# BT_Lamp_Controller.net
KiCad netlist of a schematic drawn in Altium Designer
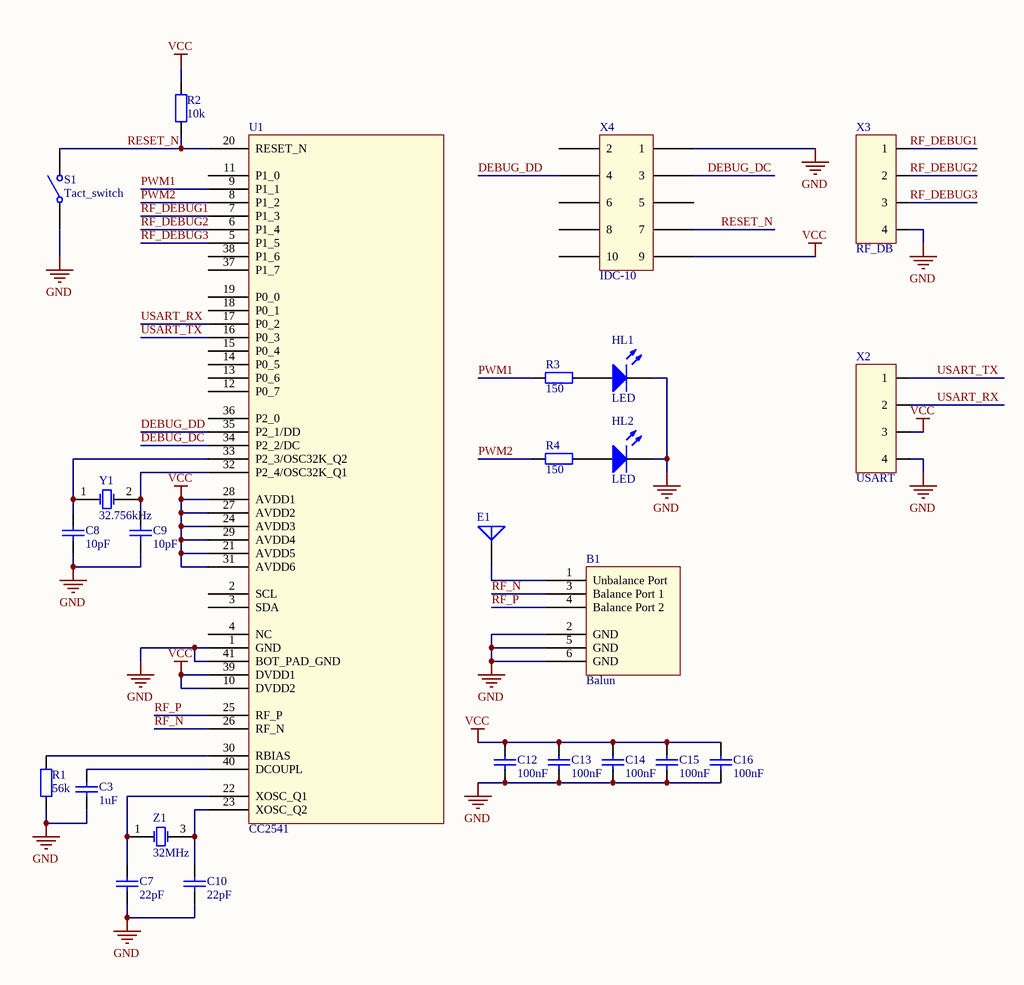
[diagram p0: BT_Lamp_Controller.SchDoc]

(export (version "E")
  (design (tool "Eeschema 10.0.6"))
  (components
    (comp (ref "B1")
      (value "Balun")
      (footprint "A_H_pcb_lib:2.4 Balun 50Ohm LFB182G45BG2D280")
      (libsource (lib "A_H_sch_lib") (part "2.4 Balun 50Ohm LFB182G45BG2D280"))
    )
    (comp (ref "C3")
      (value "1uF")
      (footprint "A_H_pcb_lib:C0603")
      (libsource (lib "A_H_sch_lib") (part "Condensator"))
    )
    (comp (ref "C7")
      (value "22pF")
      (footprint "A_H_pcb_lib:C0603")
      (libsource (lib "A_H_sch_lib") (part "Condensator"))
    )
    (comp (ref "C8")
      (value "10pF")
      (footprint "A_H_pcb_lib:C0603")
      (libsource (lib "A_H_sch_lib") (part "Condensator"))
    )
    (comp (ref "C9")
      (value "10pF")
      (footprint "A_H_pcb_lib:C0603")
      (libsource (lib "A_H_sch_lib") (part "Condensator"))
    )
    (comp (ref "C10")
      (value "22pF")
      (footprint "A_H_pcb_lib:C0603")
      (libsource (lib "A_H_sch_lib") (part "Condensator"))
    )
    (comp (ref "C12")
      (value "100nF")
      (footprint "A_H_pcb_lib:C0603")
      (libsource (lib "A_H_sch_lib") (part "Condensator"))
    )
    (comp (ref "C13")
      (value "100nF")
      (footprint "A_H_pcb_lib:C0603")
      (libsource (lib "A_H_sch_lib") (part "Condensator"))
    )
    (comp (ref "C14")
      (value "100nF")
      (footprint "A_H_pcb_lib:C0603")
      (libsource (lib "A_H_sch_lib") (part "Condensator"))
    )
    (comp (ref "C15")
      (value "100nF")
      (footprint "A_H_pcb_lib:C0603")
      (libsource (lib "A_H_sch_lib") (part "Condensator"))
    )
    (comp (ref "C16")
      (value "100nF")
      (footprint "A_H_pcb_lib:C0603")
      (libsource (lib "A_H_sch_lib") (part "Condensator"))
    )
    (comp (ref "E1")
      (value "Antenna")
      (footprint "A_H_pcb_lib:2.4 INF Antenna")
      (libsource (lib "A_H_sch_lib") (part "Antenna"))
    )
    (comp (ref "HL1")
      (value "LED")
      (footprint "A_H_pcb_lib:LED_0805")
      (libsource (lib "A_H_sch_lib") (part "LED"))
    )
    (comp (ref "HL2")
      (value "LED")
      (footprint "A_H_pcb_lib:LED_0805")
      (libsource (lib "A_H_sch_lib") (part "LED"))
    )
    (comp (ref "R1") (value "56k") (footprint "A_H_pcb_lib:R0603") (libsource (lib "") (part "Resistor_1")))
    (comp (ref "R2") (value "10k") (footprint "A_H_pcb_lib:R0603") (libsource (lib "") (part "Resistor_1")))
    (comp (ref "R3")
      (value "150")
      (footprint "A_H_pcb_lib:R0603")
      (libsource (lib "A_H_sch_lib") (part "Resistor"))
    )
    (comp (ref "R4")
      (value "150")
      (footprint "A_H_pcb_lib:R0603")
      (libsource (lib "A_H_sch_lib") (part "Resistor"))
    )
    (comp (ref "S1")
      (value "Tact_switch")
      (footprint "Tact_switch_smd")
      (libsource (lib "A_H_sch_lib") (part "Tact_switch"))
    )
    (comp (ref "U1")
      (value "CC2541")
      (footprint "A_H_pcb_lib:QFN40 6x6 0.5pitch")
      (libsource (lib "A_H_sch_lib") (part "CC2541"))
    )
    (comp (ref "X2")
      (value "USART")
      (footprint "Pins 4x2.54")
      (libsource (lib "A_H_sch_lib") (part "Pins 4x2.54"))
    )
    (comp (ref "X3")
      (value "RF_DB")
      (footprint "Pins 4x2.54")
      (libsource (lib "A_H_sch_lib") (part "Pins 4x2.54"))
    )
    (comp (ref "X4")
      (value "IDC-10")
      (footprint "A_H_pcb_lib:IDC-10")
      (libsource (lib "A_H_sch_lib") (part "IDC-10"))
    )
    (comp (ref "Y1")
      (value "32.756kHz")
      (footprint "Geyer KX - 327S 32.768kHz")
      (libsource (lib "A_H_sch_lib") (part "Crystal Oscillator"))
    )
    (comp (ref "Z1")
      (value "32MHz")
      (footprint "kx 13 12MHz")
      (libsource (lib "A_H_sch_lib") (part "KX 13 Geyer"))
    )
  )
  (nets
    (net (code "1") (name "/DEBUG_DC") (class "Default")
      (node (ref "U1") (pin "34") (pinfunction "P2_2/DC_34") (pintype "passive"))
      (node (ref "X4") (pin "3") (pinfunction "3_3") (pintype "passive"))
    )
    (net (code "2") (name "/DEBUG_DD") (class "Default")
      (node (ref "U1") (pin "35") (pinfunction "P2_1/DD_35") (pintype "passive"))
      (node (ref "X4") (pin "4") (pinfunction "4_4") (pintype "passive"))
    )
    (net (code "3") (name "/PWM1") (class "Default")
      (node (ref "R3") (pin "2") (pinfunction "2_2") (pintype "passive"))
      (node (ref "U1") (pin "9") (pinfunction "P1_1_9") (pintype "passive"))
    )
    (net (code "4") (name "/PWM2") (class "Default")
      (node (ref "R4") (pin "2") (pinfunction "2_2") (pintype "passive"))
      (node (ref "U1") (pin "8") (pinfunction "P1_2_8") (pintype "passive"))
    )
    (net (code "5") (name "/RESET_N") (class "Default")
      (node (ref "R2") (pin "1") (pinfunction "1_1") (pintype "passive"))
      (node (ref "S1") (pin "2") (pinfunction "NO_2") (pintype "passive"))
      (node (ref "U1") (pin "20") (pinfunction "RESET_N_20") (pintype "passive"))
      (node (ref "X4") (pin "7") (pinfunction "7_7") (pintype "passive"))
    )
    (net (code "6") (name "/RF_DEBUG1") (class "Default")
      (node (ref "U1") (pin "7") (pinfunction "P1_3_7") (pintype "passive"))
      (node (ref "X3") (pin "1") (pinfunction "1_1") (pintype "passive"))
    )
    (net (code "7") (name "/RF_DEBUG2") (class "Default")
      (node (ref "U1") (pin "6") (pinfunction "P1_4_6") (pintype "passive"))
      (node (ref "X3") (pin "2") (pinfunction "2_2") (pintype "passive"))
    )
    (net (code "8") (name "/RF_DEBUG3") (class "Default")
      (node (ref "U1") (pin "5") (pinfunction "P1_5_5") (pintype "passive"))
      (node (ref "X3") (pin "3") (pinfunction "3_3") (pintype "passive"))
    )
    (net (code "9") (name "/RF_N") (class "Default")
      (node (ref "B1") (pin "3") (pinfunction "Balance_Port_1_3") (pintype "passive"))
      (node (ref "U1") (pin "26") (pinfunction "RF_N_26") (pintype "passive"))
    )
    (net (code "10") (name "/RF_P") (class "Default")
      (node (ref "B1") (pin "4") (pinfunction "Balance_Port_2_4") (pintype "passive"))
      (node (ref "U1") (pin "25") (pinfunction "RF_P_25") (pintype "passive"))
    )
    (net (code "11") (name "/USART_RX") (class "Default")
      (node (ref "U1") (pin "17") (pinfunction "P0_2_17") (pintype "passive"))
      (node (ref "X2") (pin "2") (pinfunction "2_2") (pintype "passive"))
    )
    (net (code "12") (name "/USART_TX") (class "Default")
      (node (ref "U1") (pin "16") (pinfunction "P0_3_16") (pintype "passive"))
      (node (ref "X2") (pin "1") (pinfunction "1_1") (pintype "passive"))
    )
    (net (code "13") (name "GND") (class "Default")
      (node (ref "B1") (pin "2") (pinfunction "GND_2") (pintype "passive"))
      (node (ref "B1") (pin "5") (pinfunction "GND_5") (pintype "passive"))
      (node (ref "B1") (pin "6") (pinfunction "GND_6") (pintype "passive"))
      (node (ref "C10") (pin "1") (pinfunction "1_1") (pintype "passive"))
      (node (ref "C12") (pin "2") (pinfunction "2_2") (pintype "passive"))
      (node (ref "C13") (pin "2") (pinfunction "2_2") (pintype "passive"))
      (node (ref "C14") (pin "2") (pinfunction "2_2") (pintype "passive"))
      (node (ref "C15") (pin "2") (pinfunction "2_2") (pintype "passive"))
      (node (ref "C16") (pin "2") (pinfunction "2_2") (pintype "passive"))
      (node (ref "C3") (pin "1") (pinfunction "1_1") (pintype "passive"))
      (node (ref "C7") (pin "1") (pinfunction "1_1") (pintype "passive"))
      (node (ref "C8") (pin "1") (pinfunction "1_1") (pintype "passive"))
      (node (ref "C9") (pin "1") (pinfunction "1_1") (pintype "passive"))
      (node (ref "HL1") (pin "2") (pinfunction "K_2") (pintype "passive"))
      (node (ref "HL2") (pin "2") (pinfunction "K_2") (pintype "passive"))
      (node (ref "R1") (pin "1") (pinfunction "1_1") (pintype "passive"))
      (node (ref "S1") (pin "1") (pinfunction "COMMON_1") (pintype "passive"))
      (node (ref "U1") (pin "1") (pinfunction "GND_1") (pintype "passive"))
      (node (ref "U1") (pin "41") (pinfunction "BOT_PAD_GND_41") (pintype "passive"))
      (node (ref "X2") (pin "4") (pinfunction "4_4") (pintype "passive"))
      (node (ref "X3") (pin "4") (pinfunction "4_4") (pintype "passive"))
      (node (ref "X4") (pin "1") (pinfunction "1_1") (pintype "passive"))
    )
    (net (code "14") (name "Net-(B1-Unbalance_Port)") (class "Default")
      (node (ref "B1") (pin "1") (pinfunction "Unbalance_Port_1") (pintype "passive"))
      (node (ref "E1") (pin "1") (pinfunction "A_1") (pintype "passive"))
    )
    (net (code "15") (name "Net-(HL1-A)") (class "Default")
      (node (ref "HL1") (pin "1") (pinfunction "A_1") (pintype "passive"))
      (node (ref "R3") (pin "1") (pinfunction "1_1") (pintype "passive"))
    )
    (net (code "16") (name "Net-(HL2-A)") (class "Default")
      (node (ref "HL2") (pin "1") (pinfunction "A_1") (pintype "passive"))
      (node (ref "R4") (pin "1") (pinfunction "1_1") (pintype "passive"))
    )
    (net (code "17") (name "Net-(U1-DCOUPL)") (class "Default")
      (node (ref "C3") (pin "2") (pinfunction "2_2") (pintype "passive"))
      (node (ref "U1") (pin "40") (pinfunction "DCOUPL_40") (pintype "passive"))
    )
    (net (code "18") (name "Net-(U1-P2_3{slash}OSC32K_Q2)") (class "Default")
      (node (ref "C8") (pin "2") (pinfunction "2_2") (pintype "passive"))
      (node (ref "U1") (pin "33") (pinfunction "P2_3/OSC32K_Q2_33") (pintype "passive"))
      (node (ref "Y1") (pin "1") (pinfunction "OSC1_1") (pintype "passive"))
    )
    (net (code "19") (name "Net-(U1-P2_4{slash}OSC32K_Q1)") (class "Default")
      (node (ref "C9") (pin "2") (pinfunction "2_2") (pintype "passive"))
      (node (ref "U1") (pin "32") (pinfunction "P2_4/OSC32K_Q1_32") (pintype "passive"))
      (node (ref "Y1") (pin "2") (pinfunction "OSC2_2") (pintype "passive"))
    )
    (net (code "20") (name "Net-(U1-RBIAS)") (class "Default")
      (node (ref "R1") (pin "2") (pinfunction "2_2") (pintype "passive"))
      (node (ref "U1") (pin "30") (pinfunction "RBIAS_30") (pintype "passive"))
    )
    (net (code "21") (name "Net-(U1-XOSC_Q1)") (class "Default")
      (node (ref "C7") (pin "2") (pinfunction "2_2") (pintype "passive"))
      (node (ref "U1") (pin "22") (pinfunction "XOSC_Q1_22") (pintype "passive"))
      (node (ref "Z1") (pin "1") (pinfunction "OSC1_1") (pintype "passive"))
    )
    (net (code "22") (name "Net-(U1-XOSC_Q2)") (class "Default")
      (node (ref "C10") (pin "2") (pinfunction "2_2") (pintype "passive"))
      (node (ref "U1") (pin "23") (pinfunction "XOSC_Q2_23") (pintype "passive"))
      (node (ref "Z1") (pin "3") (pinfunction "OSC2_3") (pintype "passive"))
    )
    (net (code "23") (name "VCC") (class "Default")
      (node (ref "C12") (pin "1") (pinfunction "1_1") (pintype "passive"))
      (node (ref "C13") (pin "1") (pinfunction "1_1") (pintype "passive"))
      (node (ref "C14") (pin "1") (pinfunction "1_1") (pintype "passive"))
      (node (ref "C15") (pin "1") (pinfunction "1_1") (pintype "passive"))
      (node (ref "C16") (pin "1") (pinfunction "1_1") (pintype "passive"))
      (node (ref "R2") (pin "2") (pinfunction "2_2") (pintype "passive"))
      (node (ref "U1") (pin "10") (pinfunction "DVDD2_10") (pintype "passive"))
      (node (ref "U1") (pin "21") (pinfunction "AVDD5_21") (pintype "passive"))
      (node (ref "U1") (pin "24") (pinfunction "AVDD3_24") (pintype "passive"))
      (node (ref "U1") (pin "27") (pinfunction "AVDD2_27") (pintype "passive"))
      (node (ref "U1") (pin "28") (pinfunction "AVDD1_28") (pintype "passive"))
      (node (ref "U1") (pin "29") (pinfunction "AVDD4_29") (pintype "passive"))
      (node (ref "U1") (pin "31") (pinfunction "AVDD6_31") (pintype "passive"))
      (node (ref "U1") (pin "39") (pinfunction "DVDD1_39") (pintype "passive"))
      (node (ref "X2") (pin "3") (pinfunction "3_3") (pintype "passive"))
      (node (ref "X4") (pin "9") (pinfunction "9_9") (pintype "passive"))
    )
    (net (code "24") (name "unconnected-(U1-NC-Pad4)") (class "Default")
      (node (ref "U1") (pin "4") (pinfunction "NC_4") (pintype "passive"))
    )
    (net (code "25") (name "unconnected-(U1-P0_0-Pad19)") (class "Default")
      (node (ref "U1") (pin "19") (pinfunction "P0_0_19") (pintype "passive"))
    )
    (net (code "26") (name "unconnected-(U1-P0_1-Pad18)") (class "Default")
      (node (ref "U1") (pin "18") (pinfunction "P0_1_18") (pintype "passive"))
    )
    (net (code "27") (name "unconnected-(U1-P0_4-Pad15)") (class "Default")
      (node (ref "U1") (pin "15") (pinfunction "P0_4_15") (pintype "passive"))
    )
    (net (code "28") (name "unconnected-(U1-P0_5-Pad14)") (class "Default")
      (node (ref "U1") (pin "14") (pinfunction "P0_5_14") (pintype "passive"))
    )
    (net (code "29") (name "unconnected-(U1-P0_6-Pad13)") (class "Default")
      (node (ref "U1") (pin "13") (pinfunction "P0_6_13") (pintype "passive"))
    )
    (net (code "30") (name "unconnected-(U1-P0_7-Pad12)") (class "Default")
      (node (ref "U1") (pin "12") (pinfunction "P0_7_12") (pintype "passive"))
    )
    (net (code "31") (name "unconnected-(U1-P1_0-Pad11)") (class "Default")
      (node (ref "U1") (pin "11") (pinfunction "P1_0_11") (pintype "passive"))
    )
    (net (code "32") (name "unconnected-(U1-P1_6-Pad38)") (class "Default")
      (node (ref "U1") (pin "38") (pinfunction "P1_6_38") (pintype "passive"))
    )
    (net (code "33") (name "unconnected-(U1-P1_7-Pad37)") (class "Default")
      (node (ref "U1") (pin "37") (pinfunction "P1_7_37") (pintype "passive"))
    )
    (net (code "34") (name "unconnected-(U1-P2_0-Pad36)") (class "Default")
      (node (ref "U1") (pin "36") (pinfunction "P2_0_36") (pintype "passive"))
    )
    (net (code "35") (name "unconnected-(U1-SCL-Pad2)") (class "Default")
      (node (ref "U1") (pin "2") (pinfunction "SCL_2") (pintype "passive"))
    )
    (net (code "36") (name "unconnected-(U1-SDA-Pad3)") (class "Default")
      (node (ref "U1") (pin "3") (pinfunction "SDA_3") (pintype "passive"))
    )
    (net (code "37") (name "unconnected-(X4-Pad2)") (class "Default")
      (node (ref "X4") (pin "2") (pinfunction "2_2") (pintype "passive"))
    )
    (net (code "38") (name "unconnected-(X4-Pad5)") (class "Default")
      (node (ref "X4") (pin "5") (pinfunction "5_5") (pintype "passive"))
    )
    (net (code "39") (name "unconnected-(X4-Pad6)") (class "Default")
      (node (ref "X4") (pin "6") (pinfunction "6_6") (pintype "passive"))
    )
    (net (code "40") (name "unconnected-(X4-Pad8)") (class "Default")
      (node (ref "X4") (pin "8") (pinfunction "8_8") (pintype "passive"))
    )
    (net (code "41") (name "unconnected-(X4-Pad10)") (class "Default")
      (node (ref "X4") (pin "10") (pinfunction "10_10") (pintype "passive"))
    )
  )
)
